# Nwatch.net
KiCad netlist of a schematic drawn in Altium Designer
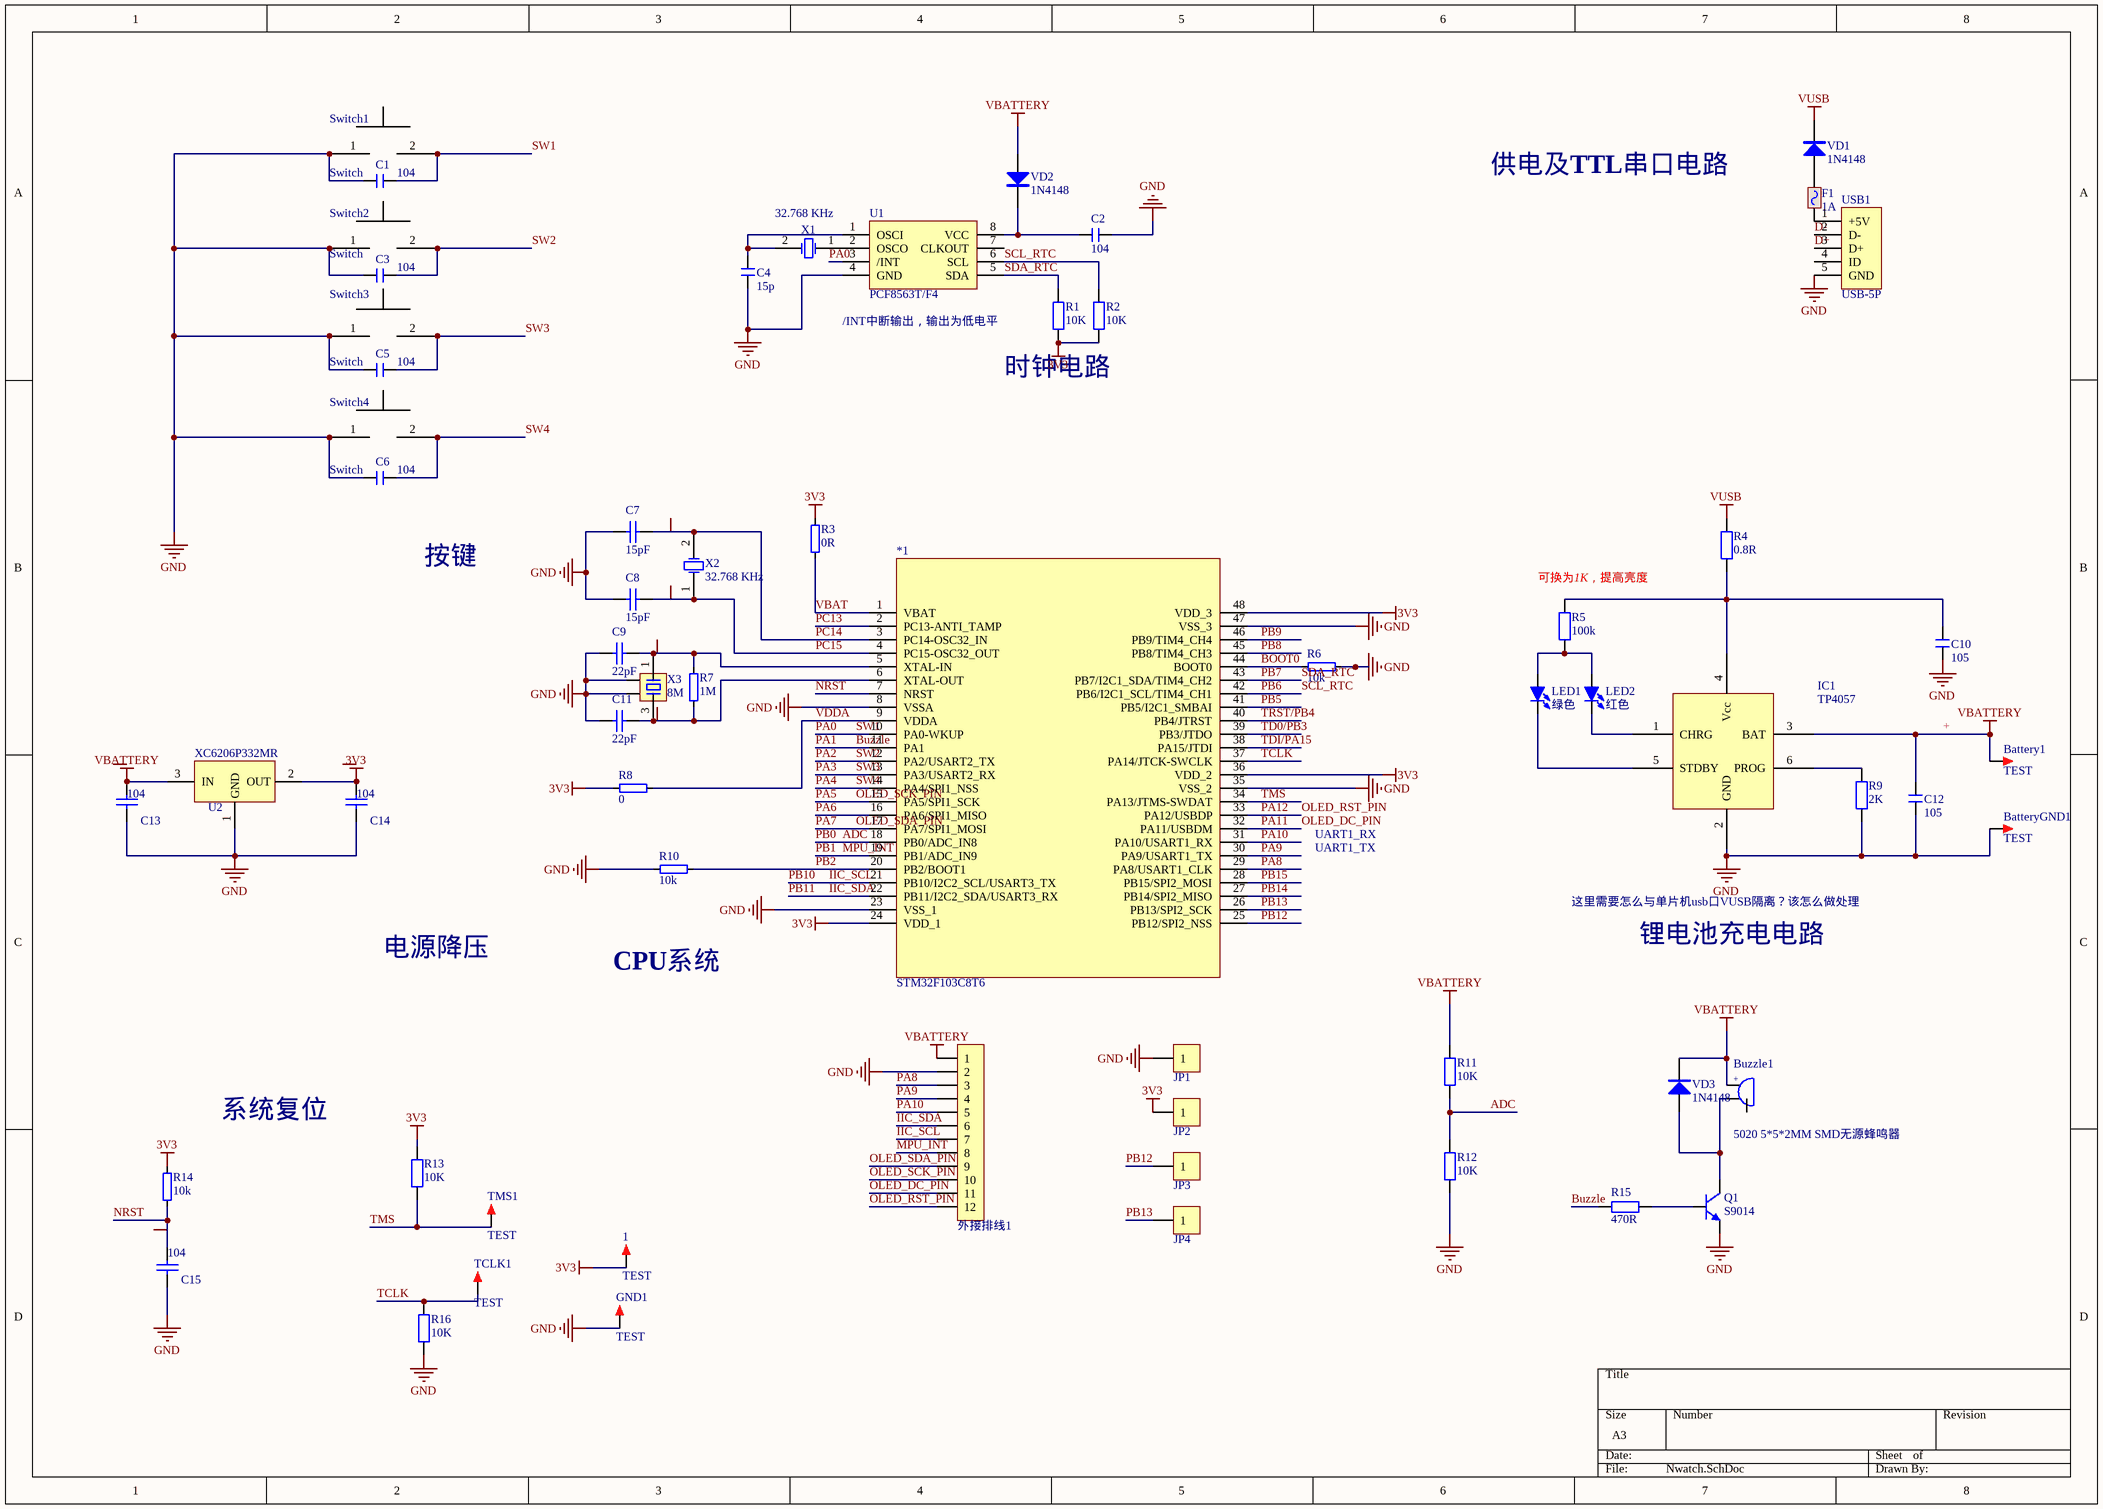
[diagram p0: Nwatch.SchDoc]

(export (version "E")
  (design (tool "Eeschema 10.0.6"))
  (components
    (comp (ref "*1")
      (value "STM32F103C8T6")
      (footprint "LQFP48 7x7_M")
      (libsource (lib "YUMMY") (part "STM32F103C8T6"))
    )
    (comp (ref "1")
      (value "TEST")
      (footprint "TEST 1.6")
      (description "测试点")
      (fields (field (name "版权归属") "源创客"))
      (libsource (lib "15.1 - 未分类器件") (part "TEST"))
    )
    (comp (ref "Battery1")
      (value "TEST")
      (footprint "TEST 1.6")
      (description "测试点")
      (fields (field (name "版权归属") "源创客"))
      (libsource (lib "15.1 - 未分类器件") (part "TEST"))
    )
    (comp (ref "BatteryGND1")
      (value "TEST")
      (footprint "TEST 1.6")
      (description "测试点")
      (fields (field (name "版权归属") "源创客"))
      (libsource (lib "15.1 - 未分类器件") (part "TEST"))
    )
    (comp (ref "Buzzle1")
      (value "5020 5*5*2MM SMD无源蜂鸣器")
      (footprint "5020 5*5*2MM SMD贴片超薄超小电磁式无源蜂鸣器")
      (description "5020 5*5*2MM SMD贴片超薄超小电磁式无源蜂鸣器")
      (libsource (lib "未分类器件") (part "5020 SMD无源蜂鸣器"))
    )
    (comp (ref "C1")
      (value "104")
      (footprint "C 0805")
      (description "无极性贴片电容")
      (fields (field (name "版权归属") "源创客"))
      (libsource (lib "电阻-电容-电感") (part "C"))
    )
    (comp (ref "C2")
      (value "104")
      (footprint "C 0805")
      (description "无极性贴片电容")
      (fields (field (name "版权归属") "源创客"))
      (libsource (lib "电阻-电容-电感") (part "C"))
    )
    (comp (ref "C3")
      (value "104")
      (footprint "C 0805")
      (description "无极性贴片电容")
      (fields (field (name "版权归属") "源创客"))
      (libsource (lib "电阻-电容-电感") (part "C"))
    )
    (comp (ref "C4")
      (value "15p")
      (footprint "C 0805")
      (description "无极性贴片电容")
      (fields (field (name "版权归属") "源创客"))
      (libsource (lib "电阻-电容-电感") (part "C"))
    )
    (comp (ref "C5")
      (value "104")
      (footprint "C 0805")
      (description "无极性贴片电容")
      (fields (field (name "版权归属") "源创客"))
      (libsource (lib "电阻-电容-电感") (part "C"))
    )
    (comp (ref "C6")
      (value "104")
      (footprint "C 0805")
      (description "无极性贴片电容")
      (fields (field (name "版权归属") "源创客"))
      (libsource (lib "电阻-电容-电感") (part "C"))
    )
    (comp (ref "C7") (value "15pF") (footprint "C 0805") (libsource (lib "改好的库") (part "Cap  贴片")))
    (comp (ref "C8") (value "15pF") (footprint "C 0805") (libsource (lib "改好的库") (part "Cap  贴片")))
    (comp (ref "C9") (value "22pF") (footprint "C 0805") (libsource (lib "改好的库") (part "Cap  贴片")))
    (comp (ref "C10")
      (value "105")
      (footprint "C 0805")
      (description "无极性贴片电容")
      (fields (field (name "版权归属") "源创客"))
      (libsource (lib "3.1   - 电阻-电容-电感") (part "C"))
    )
    (comp (ref "C11") (value "22pF") (footprint "C 0805") (libsource (lib "改好的库") (part "Cap  贴片")))
    (comp (ref "C12")
      (value "105")
      (footprint "C 0805")
      (description "无极性贴片电容")
      (fields (field (name "版权归属") "源创客"))
      (libsource (lib "3.1   - 电阻-电容-电感") (part "C"))
    )
    (comp (ref "C13") (value "104") (footprint "C 0805") (libsource (lib "") (part "Cap  贴片_1")))
    (comp (ref "C14") (value "104") (footprint "C 0805") (libsource (lib "") (part "Cap  贴片_1")))
    (comp (ref "C15") (value "104") (footprint "C 0805") (libsource (lib "") (part "Cap  贴片_1")))
    (comp (ref "F1") (value "1A") (footprint "R 0603") (libsource (lib "改好的库") (part "FUSE")))
    (comp (ref "GND1")
      (value "TEST")
      (footprint "TEST 1.6")
      (description "测试点")
      (fields (field (name "版权归属") "源创客"))
      (libsource (lib "15.1 - 未分类器件") (part "TEST"))
    )
    (comp (ref "IC1")
      (value "TP4057")
      (footprint "SOT23-6N")
      (description "500mA/600mA锂电池充电管理IC")
      (libsource (lib "1.3   - 电源类芯片") (part "TP4057/4059"))
    )
    (comp (ref "JP1")
      (value "HDR-1X1")
      (footprint "HDR-1X1")
      (description "1P接插件")
      (fields (field (name "版权归属") "源创客"))
      (libsource (lib "接插件") (part "Header 1"))
    )
    (comp (ref "JP2")
      (value "HDR-1X1")
      (footprint "HDR-1X1")
      (description "1P接插件")
      (fields (field (name "版权归属") "源创客"))
      (libsource (lib "接插件") (part "Header 1"))
    )
    (comp (ref "JP3")
      (value "HDR-1X1")
      (footprint "HDR-1X1")
      (description "1P接插件")
      (fields (field (name "版权归属") "源创客"))
      (libsource (lib "接插件") (part "Header 1"))
    )
    (comp (ref "JP4")
      (value "HDR-1X1")
      (footprint "HDR-1X1")
      (description "1P接插件")
      (fields (field (name "版权归属") "源创客"))
      (libsource (lib "接插件") (part "Header 1"))
    )
    (comp (ref "LED1")
      (value "绿色")
      (footprint "LED 0603G")
      (description "贴片LED")
      (fields (field (name "版权归属") "源创客"))
      (libsource (lib "9.1   - LED") (part "LED-SMD"))
    )
    (comp (ref "LED2")
      (value "红色")
      (footprint "LED 0603R")
      (description "贴片LED")
      (fields (field (name "版权归属") "源创客"))
      (libsource (lib "9.1   - LED") (part "LED-SMD"))
    )
    (comp (ref "Q1")
      (value "S9014")
      (footprint "SOT23-3L")
      (description "低噪放大-NPN型")
      (fields (field (name "版权归属") "源创客"))
      (libsource (lib "三极管") (part "9014-SMD"))
    )
    (comp (ref "R1")
      (value "10K")
      (footprint "R 0805")
      (description "贴片电阻")
      (fields (field (name "版权归属") "源创客"))
      (libsource (lib "电阻-电容-电感") (part "R"))
    )
    (comp (ref "R2")
      (value "10K")
      (footprint "R 0805")
      (description "贴片电阻")
      (fields (field (name "版权归属") "源创客"))
      (libsource (lib "电阻-电容-电感") (part "R"))
    )
    (comp (ref "R3") (value "0R") (footprint "R 0805") (libsource (lib "") (part "Res  贴片_1")))
    (comp (ref "R4")
      (value "0.8R")
      (footprint "R 0805")
      (description "贴片电阻")
      (fields (field (name "版权归属") "源创客"))
      (libsource (lib "3.1   - 电阻-电容-电感") (part "R"))
    )
    (comp (ref "R5")
      (value "100k")
      (footprint "R 0805")
      (description "贴片电阻")
      (fields (field (name "版权归属") "源创客"))
      (libsource (lib "3.1   - 电阻-电容-电感") (part "R"))
    )
    (comp (ref "R6") (value "10k") (footprint "R 0805") (libsource (lib "改好的库") (part "Res  贴片")))
    (comp (ref "R7") (value "1M") (footprint "R 0805") (libsource (lib "改好的库") (part "Res  贴片")))
    (comp (ref "R8") (value "0") (footprint "R 0805") (libsource (lib "改好的库") (part "Res  贴片")))
    (comp (ref "R9")
      (value "2K")
      (footprint "R 0805")
      (description "贴片电阻")
      (fields (field (name "版权归属") "源创客"))
      (libsource (lib "3.1   - 电阻-电容-电感") (part "R"))
    )
    (comp (ref "R10") (value "10k") (footprint "R 0805") (libsource (lib "改好的库") (part "Res  贴片")))
    (comp (ref "R11")
      (value "10K")
      (footprint "R 0805")
      (description "贴片电阻")
      (fields (field (name "版权归属") "源创客"))
      (libsource (lib "电阻-电容-电感") (part "R"))
    )
    (comp (ref "R12")
      (value "10K")
      (footprint "R 0805")
      (description "贴片电阻")
      (fields (field (name "版权归属") "源创客"))
      (libsource (lib "电阻-电容-电感") (part "R"))
    )
    (comp (ref "R13")
      (value "10K")
      (footprint "R 0805")
      (description "贴片电阻")
      (fields (field (name "版权归属") "源创客"))
      (libsource (lib "3.1   - 电阻-电容-电感") (part "R"))
    )
    (comp (ref "R14") (value "10k") (footprint "R 0805") (libsource (lib "改好的库") (part "Res  贴片")))
    (comp (ref "R15")
      (value "470R")
      (footprint "R 0805")
      (description "贴片电阻")
      (fields (field (name "版权归属") "源创客"))
      (libsource (lib "电阻-电容-电感") (part "R"))
    )
    (comp (ref "R16")
      (value "10K")
      (footprint "R 0805")
      (description "贴片电阻")
      (fields (field (name "版权归属") "源创客"))
      (libsource (lib "3.1   - 电阻-电容-电感") (part "R"))
    )
    (comp (ref "Switch1")
      (value "Switch")
      (footprint "侧按键")
      (description "测贴 轻触开关 2*4*3.5MM")
      (libsource (lib "按键-开关") (part "2X4X3.5侧按键"))
    )
    (comp (ref "Switch2")
      (value "Switch")
      (footprint "侧按键")
      (description "测贴 轻触开关 2*4*3.5MM")
      (libsource (lib "按键-开关") (part "2X4X3.5侧按键"))
    )
    (comp (ref "Switch3")
      (value "Switch")
      (footprint "侧按键")
      (description "测贴 轻触开关 2*4*3.5MM")
      (libsource (lib "按键-开关") (part "2X4X3.5侧按键"))
    )
    (comp (ref "Switch4")
      (value "Switch")
      (footprint "侧按键")
      (description "测贴 轻触开关 2*4*3.5MM")
      (libsource (lib "按键-开关") (part "2X4X3.5侧按键"))
    )
    (comp (ref "TCLK1")
      (value "TEST")
      (footprint "TEST 1.6")
      (description "测试点")
      (fields (field (name "版权归属") "源创客"))
      (libsource (lib "15.1 - 未分类器件") (part "TEST"))
    )
    (comp (ref "TMS1")
      (value "TEST")
      (footprint "TEST 1.6")
      (description "测试点")
      (fields (field (name "版权归属") "源创客"))
      (libsource (lib "15.1 - 未分类器件") (part "TEST"))
    )
    (comp (ref "U1")
      (value "PCF8563T/F4")
      (footprint "SOP8W_L")
      (description "时钟芯片")
      (libsource (lib "IC芯片") (part "PCF8563T"))
    )
    (comp (ref "U2") (value "XC6206P332MR") (footprint "SOT23-3L") (libsource (lib "改好的库") (part "AMS1117")))
    (comp (ref "USB1")
      (value "USB-5P")
      (footprint "USB-MICRO_A")
      (description "微型USB母座")
      (fields (field (name "版权归属") "源创客"))
      (libsource (lib "接口类") (part "USB-5P"))
    )
    (comp (ref "VD1")
      (value "1N4148")
      (footprint "SOD-323")
      (description "高速开关二极管")
      (fields (field (name "版权归属") "源创客"))
      (libsource (lib "二极管-整流桥") (part "1N4148"))
    )
    (comp (ref "VD2")
      (value "1N4148")
      (footprint "SOD-323")
      (description "高速开关二极管")
      (fields (field (name "版权归属") "源创客"))
      (libsource (lib "二极管-整流桥") (part "1N4148"))
    )
    (comp (ref "VD3")
      (value "1N4148")
      (footprint "SOD-323")
      (description "高速开关二极管")
      (fields (field (name "版权归属") "源创客"))
      (libsource (lib "二极管-整流桥") (part "1N4148"))
    )
    (comp (ref "X1")
      (value "32.768 KHz")
      (footprint "XTAL-3215")
      (description "Crystal Oscillator")
      (fields (field (name "PUBLISHER") "Altium Limited"))
      (libsource (lib "陈康迪3D打印机库") (part "XTAL"))
    )
    (comp (ref "X2")
      (value "32.768 KHz")
      (footprint "XTAL-3215")
      (description "Crystal Oscillator")
      (fields (field (name "PUBLISHER") "Altium Limited"))
      (libsource (lib "陈康迪3D打印机库") (part "XTAL"))
    )
    (comp (ref "X3")
      (value "8M")
      (footprint "XTAL-5032")
      (description "4脚晶振")
      (fields (field (name "版权归属") "源创客"))
      (libsource (lib "保险丝-晶振") (part "XTAL-4"))
    )
    (comp (ref "外接排线1")
      (value "HDR-1X12")
      (footprint "HDR-1X12")
      (description "12P接插件")
      (fields (field (name "版权归属") "源创客"))
      (libsource (lib "接插件") (part "Header 12"))
    )
  )
  (nets
    (net (code "1") (name "/ADC") (class "Default")
      (node (ref "*1") (pin "18") (pinfunction "PB0/ADC_IN8_18") (pintype "passive"))
      (node (ref "R11") (pin "1") (pinfunction "1_1") (pintype "passive"))
      (node (ref "R12") (pin "2") (pinfunction "2_2") (pintype "passive"))
    )
    (net (code "2") (name "/BOOT0") (class "Default")
      (node (ref "*1") (pin "44") (pinfunction "BOOT0_44") (pintype "passive"))
      (node (ref "R6") (pin "1") (pinfunction "1_1") (pintype "passive"))
    )
    (net (code "3") (name "/Buzzle") (class "Default")
      (node (ref "*1") (pin "11") (pinfunction "PA1_11") (pintype "passive"))
      (node (ref "R15") (pin "1") (pinfunction "1_1") (pintype "passive"))
    )
    (net (code "4") (name "/D+") (class "Default")
      (node (ref "USB1") (pin "3") (pinfunction "D+_3") (pintype "passive"))
    )
    (net (code "5") (name "/D-") (class "Default")
      (node (ref "USB1") (pin "2") (pinfunction "D-_2") (pintype "passive"))
    )
    (net (code "6") (name "/IIC_SCL") (class "Default")
      (node (ref "*1") (pin "21") (pinfunction "PB10/I2C2_SCL/USART3_TX_21") (pintype "passive"))
      (node (ref "外接排线1") (pin "7") (pinfunction "7_7") (pintype "passive"))
    )
    (net (code "7") (name "/IIC_SDA") (class "Default")
      (node (ref "*1") (pin "22") (pinfunction "PB11/I2C2_SDA/USART3_RX_22") (pintype "passive"))
      (node (ref "外接排线1") (pin "6") (pinfunction "6_6") (pintype "passive"))
    )
    (net (code "8") (name "/MPU_INT") (class "Default")
      (node (ref "*1") (pin "19") (pinfunction "PB1/ADC_IN9_19") (pintype "passive"))
      (node (ref "外接排线1") (pin "8") (pinfunction "8_8") (pintype "passive"))
    )
    (net (code "9") (name "/NRST") (class "Default")
      (node (ref "*1") (pin "7") (pinfunction "NRST_7") (pintype "passive"))
      (node (ref "C15") (pin "2") (pinfunction "2_2") (pintype "passive"))
      (node (ref "R14") (pin "1") (pinfunction "1_1") (pintype "passive"))
    )
    (net (code "10") (name "/OLED_DC_PIN") (class "Default")
      (node (ref "*1") (pin "32") (pinfunction "PA11/USBDM_32") (pintype "passive"))
      (node (ref "外接排线1") (pin "11") (pinfunction "11_11") (pintype "passive"))
    )
    (net (code "11") (name "/OLED_RST_PIN") (class "Default")
      (node (ref "*1") (pin "33") (pinfunction "PA12/USBDP_33") (pintype "passive"))
      (node (ref "外接排线1") (pin "12") (pinfunction "12_12") (pintype "passive"))
    )
    (net (code "12") (name "/OLED_SCK_PIN") (class "Default")
      (node (ref "*1") (pin "15") (pinfunction "PA5/SPI1_SCK_15") (pintype "passive"))
      (node (ref "外接排线1") (pin "10") (pinfunction "10_10") (pintype "passive"))
    )
    (net (code "13") (name "/OLED_SDA_PIN") (class "Default")
      (node (ref "*1") (pin "17") (pinfunction "PA7/SPI1_MOSI_17") (pintype "passive"))
      (node (ref "外接排线1") (pin "9") (pinfunction "9_9") (pintype "passive"))
    )
    (net (code "14") (name "/PA0") (class "Default")
      (node (ref "*1") (pin "10") (pinfunction "PA0-WKUP_10") (pintype "passive"))
      (node (ref "C1") (pin "2") (pinfunction "2_2") (pintype "passive"))
      (node (ref "Switch1") (pin "2") (pinfunction "2_2") (pintype "passive"))
      (node (ref "U1") (pin "3") (pinfunction "/INT_3") (pintype "passive"))
    )
    (net (code "15") (name "/PA2") (class "Default")
      (node (ref "*1") (pin "12") (pinfunction "PA2/USART2_TX_12") (pintype "passive"))
      (node (ref "C3") (pin "2") (pinfunction "2_2") (pintype "passive"))
      (node (ref "Switch2") (pin "2") (pinfunction "2_2") (pintype "passive"))
    )
    (net (code "16") (name "/PA3") (class "Default")
      (node (ref "*1") (pin "13") (pinfunction "PA3/USART2_RX_13") (pintype "passive"))
      (node (ref "C5") (pin "2") (pinfunction "2_2") (pintype "passive"))
      (node (ref "Switch3") (pin "2") (pinfunction "2_2") (pintype "passive"))
    )
    (net (code "17") (name "/PA4") (class "Default")
      (node (ref "*1") (pin "14") (pinfunction "PA4/SPI1_NSS_14") (pintype "passive"))
      (node (ref "C6") (pin "2") (pinfunction "2_2") (pintype "passive"))
      (node (ref "Switch4") (pin "2") (pinfunction "2_2") (pintype "passive"))
    )
    (net (code "18") (name "/PA6") (class "Default")
      (node (ref "*1") (pin "16") (pinfunction "PA6/SPI1_MISO_16") (pintype "passive"))
    )
    (net (code "19") (name "/PA8") (class "Default")
      (node (ref "*1") (pin "29") (pinfunction "PA8/USART1_CLK_29") (pintype "passive"))
      (node (ref "外接排线1") (pin "3") (pinfunction "3_3") (pintype "passive"))
    )
    (net (code "20") (name "/PA9") (class "Default")
      (node (ref "*1") (pin "30") (pinfunction "PA9/USART1_TX_30") (pintype "passive"))
      (node (ref "外接排线1") (pin "4") (pinfunction "4_4") (pintype "passive"))
    )
    (net (code "21") (name "/PA10") (class "Default")
      (node (ref "*1") (pin "31") (pinfunction "PA10/USART1_RX_31") (pintype "passive"))
      (node (ref "外接排线1") (pin "5") (pinfunction "5_5") (pintype "passive"))
    )
    (net (code "22") (name "/PB2") (class "Default")
      (node (ref "*1") (pin "20") (pinfunction "PB2/BOOT1_20") (pintype "passive"))
      (node (ref "R10") (pin "2") (pinfunction "2_2") (pintype "passive"))
    )
    (net (code "23") (name "/PB5") (class "Default")
      (node (ref "*1") (pin "41") (pinfunction "PB5/I2C1_SMBAI_41") (pintype "passive"))
    )
    (net (code "24") (name "/PB6") (class "Default")
      (node (ref "*1") (pin "42") (pinfunction "PB6/I2C1_SCL/TIM4_CH1_42") (pintype "passive"))
      (node (ref "R2") (pin "2") (pinfunction "2_2") (pintype "passive"))
      (node (ref "U1") (pin "6") (pinfunction "SCL_6") (pintype "passive"))
    )
    (net (code "25") (name "/PB7") (class "Default")
      (node (ref "*1") (pin "43") (pinfunction "PB7/I2C1_SDA/TIM4_CH2_43") (pintype "passive"))
      (node (ref "R1") (pin "2") (pinfunction "2_2") (pintype "passive"))
      (node (ref "U1") (pin "5") (pinfunction "SDA_5") (pintype "passive"))
    )
    (net (code "26") (name "/PB8") (class "Default")
      (node (ref "*1") (pin "45") (pinfunction "PB8/TIM4_CH3_45") (pintype "passive"))
    )
    (net (code "27") (name "/PB9") (class "Default")
      (node (ref "*1") (pin "46") (pinfunction "PB9/TIM4_CH4_46") (pintype "passive"))
    )
    (net (code "28") (name "/PB12") (class "Default")
      (node (ref "*1") (pin "25") (pinfunction "PB12/SPI2_NSS_25") (pintype "passive"))
      (node (ref "JP3") (pin "1") (pinfunction "1_1") (pintype "passive"))
    )
    (net (code "29") (name "/PB13") (class "Default")
      (node (ref "*1") (pin "26") (pinfunction "PB13/SPI2_SCK_26") (pintype "passive"))
      (node (ref "JP4") (pin "1") (pinfunction "1_1") (pintype "passive"))
    )
    (net (code "30") (name "/PB14") (class "Default")
      (node (ref "*1") (pin "27") (pinfunction "PB14/SPI2_MISO_27") (pintype "passive"))
    )
    (net (code "31") (name "/PB15") (class "Default")
      (node (ref "*1") (pin "28") (pinfunction "PB15/SPI2_MOSI_28") (pintype "passive"))
    )
    (net (code "32") (name "/PC13") (class "Default")
      (node (ref "*1") (pin "2") (pinfunction "PC13-ANTI_TAMP_2") (pintype "passive"))
    )
    (net (code "33") (name "/PC14") (class "Default")
      (node (ref "*1") (pin "3") (pinfunction "PC14-OSC32_IN_3") (pintype "passive"))
      (node (ref "C7") (pin "2") (pinfunction "2_2") (pintype "passive"))
      (node (ref "X2") (pin "2") (pinfunction "OSC2_2") (pintype "passive"))
    )
    (net (code "34") (name "/PC15") (class "Default")
      (node (ref "*1") (pin "4") (pinfunction "PC15-OSC32_OUT_4") (pintype "passive"))
      (node (ref "C8") (pin "2") (pinfunction "2_2") (pintype "passive"))
      (node (ref "X2") (pin "1") (pinfunction "OSC1_1") (pintype "passive"))
    )
    (net (code "35") (name "/TCLK") (class "Default")
      (node (ref "*1") (pin "37") (pinfunction "PA14/JTCK-SWCLK_37") (pintype "passive"))
      (node (ref "R16") (pin "2") (pinfunction "2_2") (pintype "passive"))
      (node (ref "TCLK1") (pin "1") (pinfunction "1_1") (pintype "passive"))
    )
    (net (code "36") (name "/TD0{slash}PB3") (class "Default")
      (node (ref "*1") (pin "39") (pinfunction "PB3/JTDO_39") (pintype "passive"))
    )
    (net (code "37") (name "/TDI{slash}PA15") (class "Default")
      (node (ref "*1") (pin "38") (pinfunction "PA15/JTDI_38") (pintype "passive"))
    )
    (net (code "38") (name "/TMS") (class "Default")
      (node (ref "*1") (pin "34") (pinfunction "PA13/JTMS-SWDAT_34") (pintype "passive"))
      (node (ref "R13") (pin "1") (pinfunction "1_1") (pintype "passive"))
      (node (ref "TMS1") (pin "1") (pinfunction "1_1") (pintype "passive"))
    )
    (net (code "39") (name "/TRST{slash}PB4") (class "Default")
      (node (ref "*1") (pin "40") (pinfunction "PB4/JTRST_40") (pintype "passive"))
    )
    (net (code "40") (name "/VBAT") (class "Default")
      (node (ref "*1") (pin "1") (pinfunction "VBAT_1") (pintype "passive"))
      (node (ref "R3") (pin "2") (pinfunction "2_2") (pintype "passive"))
    )
    (net (code "41") (name "/VDDA") (class "Default")
      (node (ref "*1") (pin "9") (pinfunction "VDDA_9") (pintype "passive"))
      (node (ref "R8") (pin "2") (pinfunction "2_2") (pintype "passive"))
    )
    (net (code "42") (name "3V3") (class "Default")
      (node (ref "*1") (pin "24") (pinfunction "VDD_1_24") (pintype "passive"))
      (node (ref "*1") (pin "36") (pinfunction "VDD_2_36") (pintype "passive"))
      (node (ref "*1") (pin "48") (pinfunction "VDD_3_48") (pintype "passive"))
      (node (ref "1") (pin "1") (pinfunction "1_1") (pintype "passive"))
      (node (ref "C14") (pin "2") (pinfunction "2_2") (pintype "passive"))
      (node (ref "JP2") (pin "1") (pinfunction "1_1") (pintype "passive"))
      (node (ref "R1") (pin "1") (pinfunction "1_1") (pintype "passive"))
      (node (ref "R13") (pin "2") (pinfunction "2_2") (pintype "passive"))
      (node (ref "R14") (pin "2") (pinfunction "2_2") (pintype "passive"))
      (node (ref "R2") (pin "1") (pinfunction "1_1") (pintype "passive"))
      (node (ref "R3") (pin "1") (pinfunction "1_1") (pintype "passive"))
      (node (ref "R8") (pin "1") (pinfunction "1_1") (pintype "passive"))
      (node (ref "U2") (pin "2") (pinfunction "OUT_2") (pintype "passive"))
    )
    (net (code "43") (name "GND") (class "Default")
      (node (ref "*1") (pin "23") (pinfunction "VSS_1_23") (pintype "passive"))
      (node (ref "*1") (pin "35") (pinfunction "VSS_2_35") (pintype "passive"))
      (node (ref "*1") (pin "47") (pinfunction "VSS_3_47") (pintype "passive"))
      (node (ref "*1") (pin "8") (pinfunction "VSSA_8") (pintype "passive"))
      (node (ref "BatteryGND1") (pin "1") (pinfunction "1_1") (pintype "passive"))
      (node (ref "C1") (pin "1") (pinfunction "1_1") (pintype "passive"))
      (node (ref "C10") (pin "1") (pinfunction "1_1") (pintype "passive"))
      (node (ref "C11") (pin "1") (pinfunction "1_1") (pintype "passive"))
      (node (ref "C12") (pin "1") (pinfunction "1_1") (pintype "passive"))
      (node (ref "C13") (pin "1") (pinfunction "1_1") (pintype "passive"))
      (node (ref "C14") (pin "1") (pinfunction "1_1") (pintype "passive"))
      (node (ref "C15") (pin "1") (pinfunction "1_1") (pintype "passive"))
      (node (ref "C2") (pin "2") (pinfunction "2_2") (pintype "passive"))
      (node (ref "C3") (pin "1") (pinfunction "1_1") (pintype "passive"))
      (node (ref "C4") (pin "1") (pinfunction "1_1") (pintype "passive"))
      (node (ref "C5") (pin "1") (pinfunction "1_1") (pintype "passive"))
      (node (ref "C6") (pin "1") (pinfunction "1_1") (pintype "passive"))
      (node (ref "C7") (pin "1") (pinfunction "1_1") (pintype "passive"))
      (node (ref "C8") (pin "1") (pinfunction "1_1") (pintype "passive"))
      (node (ref "C9") (pin "1") (pinfunction "1_1") (pintype "passive"))
      (node (ref "GND1") (pin "1") (pinfunction "1_1") (pintype "passive"))
      (node (ref "IC1") (pin "2") (pinfunction "GND_2") (pintype "passive"))
      (node (ref "JP1") (pin "1") (pinfunction "1_1") (pintype "passive"))
      (node (ref "Q1") (pin "2") (pinfunction "E_2") (pintype "passive"))
      (node (ref "R10") (pin "1") (pinfunction "1_1") (pintype "passive"))
      (node (ref "R12") (pin "1") (pinfunction "1_1") (pintype "passive"))
      (node (ref "R16") (pin "1") (pinfunction "1_1") (pintype "passive"))
      (node (ref "R6") (pin "2") (pinfunction "2_2") (pintype "passive"))
      (node (ref "R9") (pin "1") (pinfunction "1_1") (pintype "passive"))
      (node (ref "Switch1") (pin "1") (pinfunction "1_1") (pintype "passive"))
      (node (ref "Switch2") (pin "1") (pinfunction "1_1") (pintype "passive"))
      (node (ref "Switch3") (pin "1") (pinfunction "1_1") (pintype "passive"))
      (node (ref "Switch4") (pin "1") (pinfunction "1_1") (pintype "passive"))
      (node (ref "U1") (pin "4") (pinfunction "GND_4") (pintype "passive"))
      (node (ref "U2") (pin "1") (pinfunction "GND_1") (pintype "passive"))
      (node (ref "USB1") (pin "5") (pinfunction "GND_5") (pintype "passive"))
      (node (ref "X3") (pin "2") (pinfunction "2_2") (pintype "passive"))
      (node (ref "X3") (pin "4") (pinfunction "4_4") (pintype "passive"))
      (node (ref "外接排线1") (pin "2") (pinfunction "2_2") (pintype "passive"))
    )
    (net (code "44") (name "Net-(*1-XTAL-IN)") (class "Default")
      (node (ref "*1") (pin "5") (pinfunction "XTAL-IN_5") (pintype "passive"))
      (node (ref "C9") (pin "2") (pinfunction "2_2") (pintype "passive"))
      (node (ref "R7") (pin "2") (pinfunction "2_2") (pintype "passive"))
      (node (ref "X3") (pin "1") (pinfunction "1_1") (pintype "passive"))
    )
    (net (code "45") (name "Net-(*1-XTAL-OUT)") (class "Default")
      (node (ref "*1") (pin "6") (pinfunction "XTAL-OUT_6") (pintype "passive"))
      (node (ref "C11") (pin "2") (pinfunction "2_2") (pintype "passive"))
      (node (ref "R7") (pin "1") (pinfunction "1_1") (pintype "passive"))
      (node (ref "X3") (pin "3") (pinfunction "3_3") (pintype "passive"))
    )
    (net (code "46") (name "Net-(IC1-CHRG)") (class "Default")
      (node (ref "IC1") (pin "1") (pinfunction "CHRG_1") (pintype "passive"))
      (node (ref "LED2") (pin "2") (pinfunction "K_2") (pintype "passive"))
    )
    (net (code "47") (name "Net-(IC1-PROG)") (class "Default")
      (node (ref "IC1") (pin "6") (pinfunction "PROG_6") (pintype "passive"))
      (node (ref "R9") (pin "2") (pinfunction "2_2") (pintype "passive"))
    )
    (net (code "48") (name "Net-(IC1-STDBY)") (class "Default")
      (node (ref "IC1") (pin "5") (pinfunction "STDBY_5") (pintype "passive"))
      (node (ref "LED1") (pin "2") (pinfunction "K_2") (pintype "passive"))
    )
    (net (code "49") (name "Net-(IC1-Vcc)") (class "Default")
      (node (ref "C10") (pin "2") (pinfunction "2_2") (pintype "passive"))
      (node (ref "IC1") (pin "4") (pinfunction "Vcc_4") (pintype "passive"))
      (node (ref "R4") (pin "1") (pinfunction "1_1") (pintype "passive"))
      (node (ref "R5") (pin "2") (pinfunction "2_2") (pintype "passive"))
    )
    (net (code "50") (name "Net-(LED1-A)") (class "Default")
      (node (ref "LED1") (pin "1") (pinfunction "A_1") (pintype "passive"))
      (node (ref "LED2") (pin "1") (pinfunction "A_1") (pintype "passive"))
      (node (ref "R5") (pin "1") (pinfunction "1_1") (pintype "passive"))
    )
    (net (code "51") (name "Net-(Q1-B)") (class "Default")
      (node (ref "Q1") (pin "1") (pinfunction "B_1") (pintype "passive"))
      (node (ref "R15") (pin "2") (pinfunction "2_2") (pintype "passive"))
    )
    (net (code "52") (name "Net-(Q1-C)") (class "Default")
      (node (ref "Buzzle1") (pin "2") (pinfunction "2_2") (pintype "passive"))
      (node (ref "Q1") (pin "3") (pinfunction "C_3") (pintype "passive"))
      (node (ref "VD3") (pin "1") (pinfunction "A_1") (pintype "passive"))
    )
    (net (code "53") (name "Net-(U1-OSCI)") (class "Default")
      (node (ref "C4") (pin "2") (pinfunction "2_2") (pintype "passive"))
      (node (ref "U1") (pin "1") (pinfunction "OSCI_1") (pintype "passive"))
      (node (ref "X1") (pin "2") (pinfunction "OSC2_2") (pintype "passive"))
    )
    (net (code "54") (name "Net-(U1-OSCO)") (class "Default")
      (node (ref "U1") (pin "2") (pinfunction "OSCO_2") (pintype "passive"))
      (node (ref "X1") (pin "1") (pinfunction "OSC1_1") (pintype "passive"))
    )
    (net (code "55") (name "Net-(U1-VCC)") (class "Default")
      (node (ref "C2") (pin "1") (pinfunction "1_1") (pintype "passive"))
      (node (ref "U1") (pin "8") (pinfunction "VCC_8") (pintype "passive"))
      (node (ref "VD2") (pin "2") (pinfunction "K_2") (pintype "passive"))
    )
    (net (code "56") (name "Net-(USB1-+5V)") (class "Default")
      (node (ref "F1") (pin "2") (pinfunction "2_2") (pintype "passive"))
      (node (ref "USB1") (pin "1") (pinfunction "+5V_1") (pintype "passive"))
    )
    (net (code "57") (name "Net-(VD1-A)") (class "Default")
      (node (ref "F1") (pin "1") (pinfunction "1_1") (pintype "passive"))
      (node (ref "VD1") (pin "1") (pinfunction "A_1") (pintype "passive"))
    )
    (net (code "58") (name "VBATTERY") (class "Default")
      (node (ref "Battery1") (pin "1") (pinfunction "1_1") (pintype "passive"))
      (node (ref "Buzzle1") (pin "1") (pinfunction "1_1") (pintype "passive"))
      (node (ref "C12") (pin "2") (pinfunction "2_2") (pintype "passive"))
      (node (ref "C13") (pin "2") (pinfunction "2_2") (pintype "passive"))
      (node (ref "IC1") (pin "3") (pinfunction "BAT_3") (pintype "passive"))
      (node (ref "R11") (pin "2") (pinfunction "2_2") (pintype "passive"))
      (node (ref "U2") (pin "3") (pinfunction "IN_3") (pintype "passive"))
      (node (ref "VD2") (pin "1") (pinfunction "A_1") (pintype "passive"))
      (node (ref "VD3") (pin "2") (pinfunction "K_2") (pintype "passive"))
      (node (ref "外接排线1") (pin "1") (pinfunction "1_1") (pintype "passive"))
    )
    (net (code "59") (name "VUSB") (class "Default")
      (node (ref "R4") (pin "2") (pinfunction "2_2") (pintype "passive"))
      (node (ref "VD1") (pin "2") (pinfunction "K_2") (pintype "passive"))
    )
    (net (code "60") (name "unconnected-(Buzzle1-Pad3)") (class "Default")
      (node (ref "Buzzle1") (pin "3") (pinfunction "3_3") (pintype "passive"))
    )
    (net (code "61") (name "unconnected-(U1-CLKOUT-Pad7)") (class "Default")
      (node (ref "U1") (pin "7") (pinfunction "CLKOUT_7") (pintype "passive"))
    )
    (net (code "62") (name "unconnected-(USB1-ID-Pad4)") (class "Default")
      (node (ref "USB1") (pin "4") (pinfunction "ID_4") (pintype "passive"))
    )
  )
)
